# joule_thief_v5.net
KiCad netlist of a schematic drawn in EAGLE
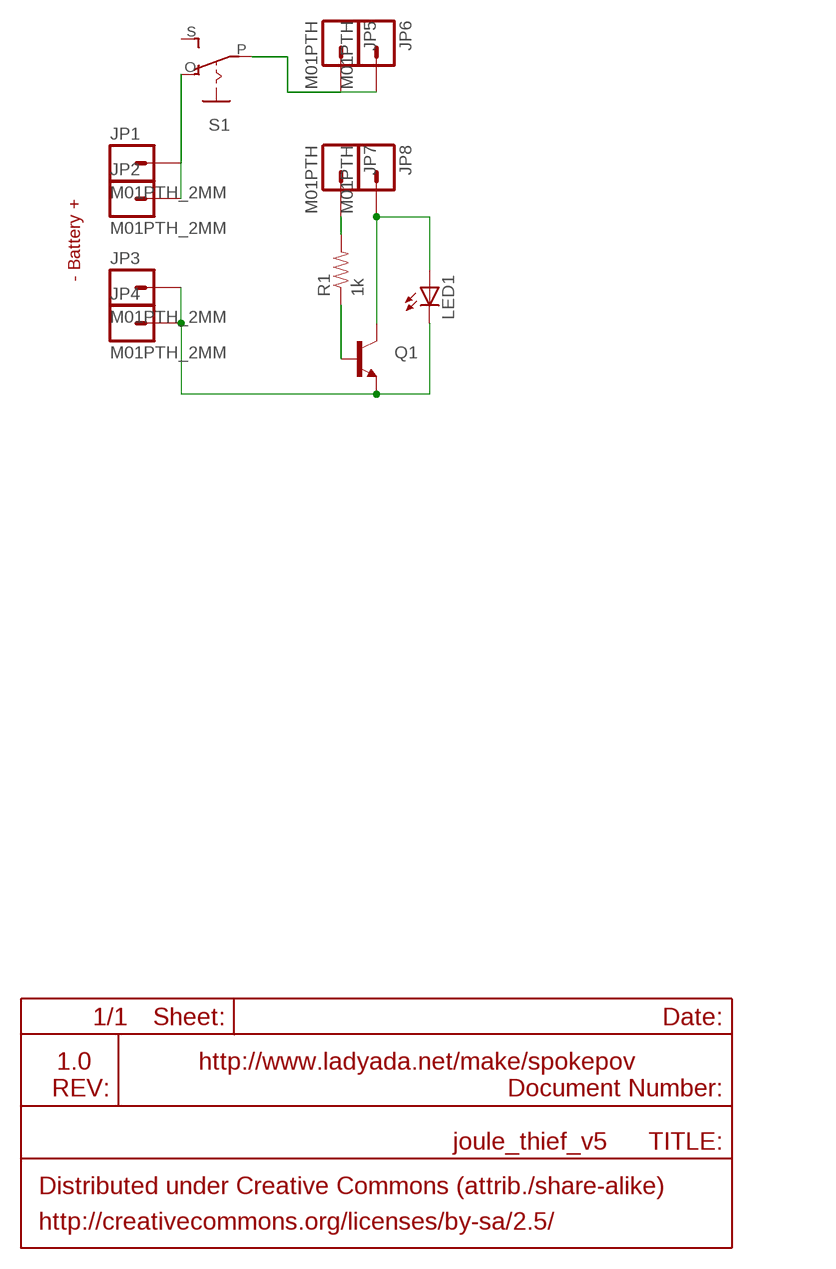
[diagram p0: schematic, sheet 1]

(export (version "E")
  (design (tool "Eeschema 10.0.6"))
  (components
    (comp (ref "JP1")
      (value "M01PTH_2MM")
      (footprint "eagle-import:1X01_2MM")
      (libsource (lib "eagle-import") (part "M01PTH_2MM"))
    )
    (comp (ref "JP2")
      (value "M01PTH_2MM")
      (footprint "eagle-import:1X01_2MM")
      (libsource (lib "eagle-import") (part "M01PTH_2MM"))
    )
    (comp (ref "JP3")
      (value "M01PTH_2MM")
      (footprint "eagle-import:1X01_2MM")
      (libsource (lib "eagle-import") (part "M01PTH_2MM"))
    )
    (comp (ref "JP4")
      (value "M01PTH_2MM")
      (footprint "eagle-import:1X01_2MM")
      (libsource (lib "eagle-import") (part "M01PTH_2MM"))
    )
    (comp (ref "JP5")
      (value "M01PTH")
      (footprint "eagle-import:1X01")
      (libsource (lib "eagle-import") (part "M01PTH"))
    )
    (comp (ref "JP6")
      (value "M01PTH")
      (footprint "eagle-import:1X01")
      (libsource (lib "eagle-import") (part "M01PTH"))
    )
    (comp (ref "JP7")
      (value "M01PTH")
      (footprint "eagle-import:1X01")
      (libsource (lib "eagle-import") (part "M01PTH"))
    )
    (comp (ref "JP8")
      (value "M01PTH")
      (footprint "eagle-import:1X01")
      (libsource (lib "eagle-import") (part "M01PTH"))
    )
    (comp (ref "LED1")
      (value "LED5MM")
      (footprint "eagle-import:LED5MM")
      (libsource (lib "eagle-import") (part "LED5MM"))
    )
    (comp (ref "Q1")
      (value "TRANSISTOR_NPNTO-92-AMMO")
      (footprint "eagle-import:TO-92-AMMO")
      (libsource (lib "eagle-import") (part "TRANSISTOR_NPNTO-92-AMMO"))
    )
    (comp (ref "R1")
      (value "1k")
      (footprint "eagle-import:AXIAL-0.3")
      (libsource (lib "eagle-import") (part "RESISTORAXIAL-0.3"))
    )
    (comp (ref "S1")
      (value "EG1218S")
      (footprint "eagle-import:EG1218")
      (libsource (lib "eagle-import") (part "EG1218S"))
    )
  )
  (nets
    (net (code "1") (name "Net-(JP1-Pad1)") (class "Default")
      (node (ref "JP1") (pin "1") (pinfunction "1_1") (pintype "passive"))
      (node (ref "JP2") (pin "1") (pinfunction "1_1") (pintype "passive"))
      (node (ref "S1") (pin "O") (pinfunction "O_O") (pintype "passive"))
    )
    (net (code "2") (name "Net-(JP5-Pad1)") (class "Default")
      (node (ref "JP5") (pin "1") (pinfunction "1_1") (pintype "passive"))
      (node (ref "JP6") (pin "1") (pinfunction "1_1") (pintype "passive"))
      (node (ref "S1") (pin "P") (pinfunction "P_P") (pintype "passive"))
    )
    (net (code "3") (name "Net-(LED1-C)") (class "Default")
      (node (ref "JP3") (pin "1") (pinfunction "1_1") (pintype "passive"))
      (node (ref "JP4") (pin "1") (pinfunction "1_1") (pintype "passive"))
      (node (ref "LED1") (pin "K") (pinfunction "C_K") (pintype "passive"))
      (node (ref "Q1") (pin "1") (pinfunction "E_1") (pintype "passive"))
    )
    (net (code "4") (name "Net-(Q1-B)") (class "Default")
      (node (ref "Q1") (pin "2") (pinfunction "B_2") (pintype "passive"))
      (node (ref "R1") (pin "P$1") (pinfunction "1_P$1") (pintype "passive"))
    )
    (net (code "5") (name "Net-(Q1-C)") (class "Default")
      (node (ref "JP8") (pin "1") (pinfunction "1_1") (pintype "passive"))
      (node (ref "LED1") (pin "A") (pinfunction "A_A") (pintype "passive"))
      (node (ref "Q1") (pin "3") (pinfunction "C_3") (pintype "passive"))
    )
    (net (code "6") (name "Net-(R1-2)") (class "Default")
      (node (ref "JP7") (pin "1") (pinfunction "1_1") (pintype "passive"))
      (node (ref "R1") (pin "P$2") (pinfunction "2_P$2") (pintype "passive"))
    )
    (net (code "7") (name "unconnected-(S1-PadS)") (class "Default")
      (node (ref "S1") (pin "S") (pinfunction "S_S") (pintype "passive"))
    )
  )
)
